# pwm-enable.net
KiCad netlist of a schematic drawn in Altium Designer
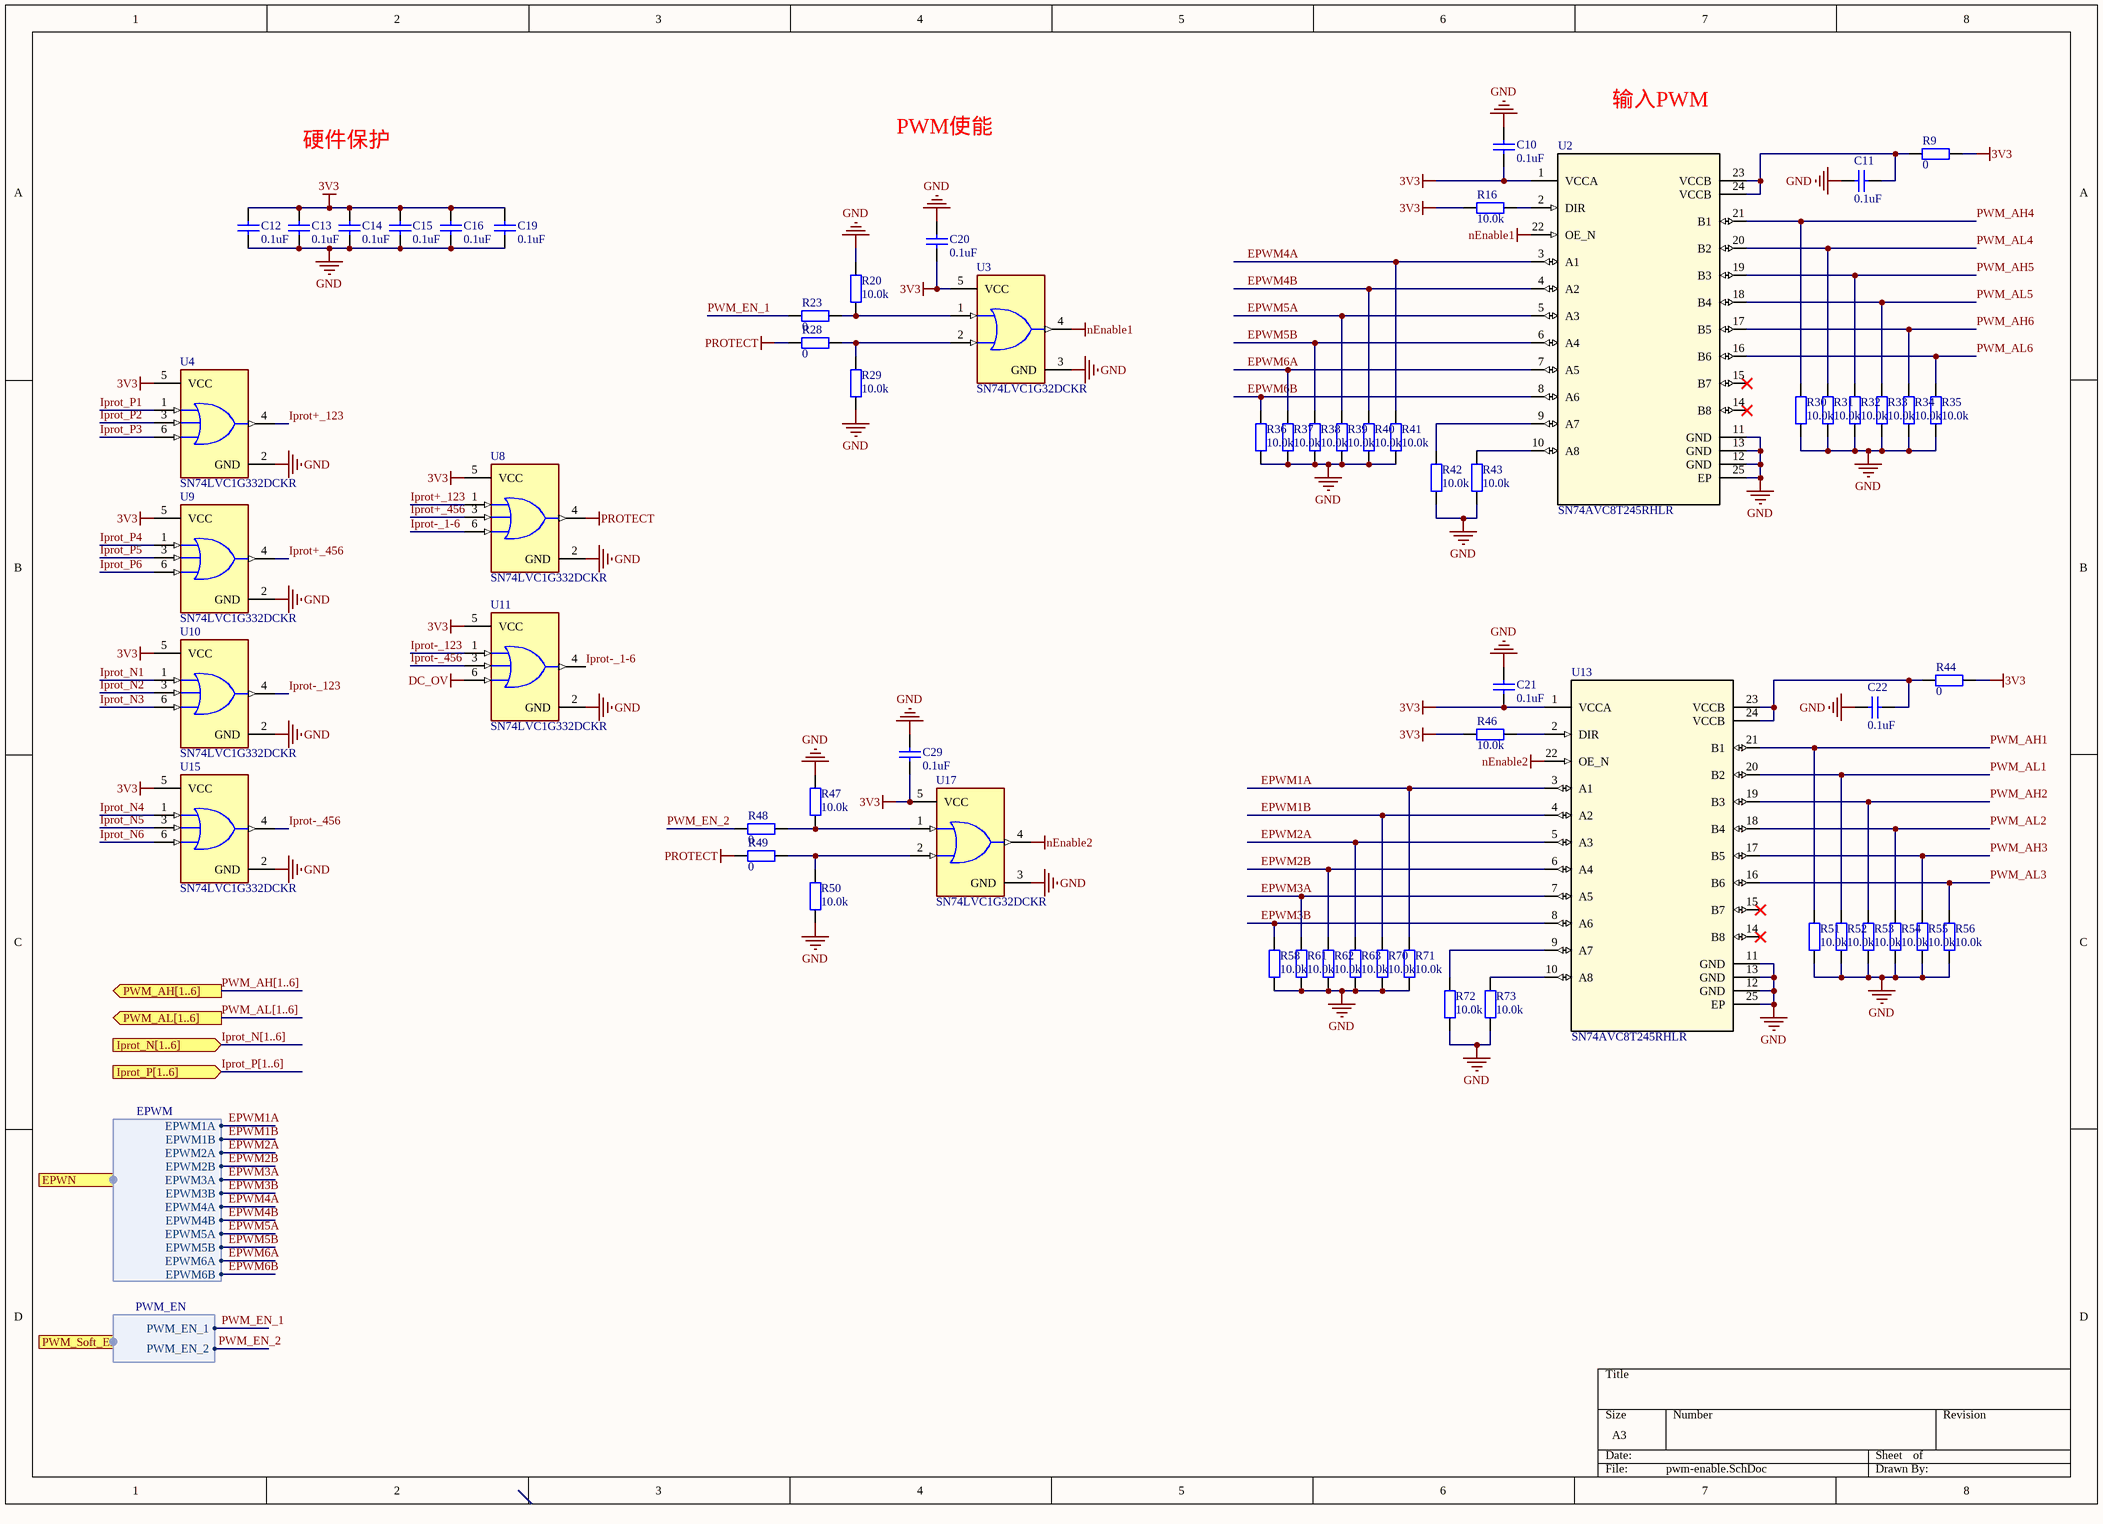
[diagram p0: pwm-enable.SchDoc]

(export (version "E")
  (design (tool "Eeschema 10.0.6"))
  (components
    (comp (ref "C10")
      (value "0.1uF")
      (footprint "CAPC1608X06N")
      (description "Capacitor")
      (fields (field (name "PUBLISHER") "Altium Limited"))
      (libsource (lib "Simscale") (part "Cap"))
    )
    (comp (ref "C11")
      (value "0.1uF")
      (footprint "CAPC1608X06N")
      (description "Capacitor")
      (fields (field (name "PUBLISHER") "Altium Limited"))
      (libsource (lib "Simscale") (part "Cap"))
    )
    (comp (ref "C12")
      (value "0.1uF")
      (footprint "CAPC1608X06N")
      (description "Capacitor")
      (fields (field (name "PUBLISHER") "Altium Limited"))
      (libsource (lib "Simscale") (part "Cap"))
    )
    (comp (ref "C13")
      (value "0.1uF")
      (footprint "CAPC1608X06N")
      (description "Capacitor")
      (fields (field (name "PUBLISHER") "Altium Limited"))
      (libsource (lib "Simscale") (part "Cap"))
    )
    (comp (ref "C14")
      (value "0.1uF")
      (footprint "CAPC1608X06N")
      (description "Capacitor")
      (fields (field (name "PUBLISHER") "Altium Limited"))
      (libsource (lib "Simscale") (part "Cap"))
    )
    (comp (ref "C15")
      (value "0.1uF")
      (footprint "CAPC1608X06N")
      (description "Capacitor")
      (fields (field (name "PUBLISHER") "Altium Limited"))
      (libsource (lib "Simscale") (part "Cap"))
    )
    (comp (ref "C16")
      (value "0.1uF")
      (footprint "CAPC1608X06N")
      (description "Capacitor")
      (fields (field (name "PUBLISHER") "Altium Limited"))
      (libsource (lib "Simscale") (part "Cap"))
    )
    (comp (ref "C19")
      (value "0.1uF")
      (footprint "CAPC1608X06N")
      (description "Capacitor")
      (fields (field (name "PUBLISHER") "Altium Limited"))
      (libsource (lib "Simscale") (part "Cap"))
    )
    (comp (ref "C20")
      (value "0.1uF")
      (footprint "CAPC1608X06N")
      (description "Capacitor")
      (fields (field (name "PUBLISHER") "Altium Limited"))
      (libsource (lib "Simscale") (part "Cap"))
    )
    (comp (ref "C21")
      (value "0.1uF")
      (footprint "CAPC1608X06N")
      (description "Capacitor")
      (fields (field (name "PUBLISHER") "Altium Limited"))
      (libsource (lib "Simscale") (part "Cap"))
    )
    (comp (ref "C22")
      (value "0.1uF")
      (footprint "CAPC1608X06N")
      (description "Capacitor")
      (fields (field (name "PUBLISHER") "Altium Limited"))
      (libsource (lib "Simscale") (part "Cap"))
    )
    (comp (ref "C29")
      (value "0.1uF")
      (footprint "CAPC1608X06N")
      (description "Capacitor")
      (fields (field (name "PUBLISHER") "Altium Limited"))
      (libsource (lib "Simscale") (part "Cap"))
    )
    (comp (ref "R9")
      (value "0")
      (footprint "RESC1608X05N")
      (description "Resistor 0402")
      (fields (field (name "PUBLISHER") "Altium Limited"))
      (libsource (lib "Soardra") (part "Res"))
    )
    (comp (ref "R16")
      (value "10.0k")
      (footprint "RESC1608X05N")
      (description "贴片电阻")
      (libsource (lib "") (part "0603 100KΩ (1003) 1%_4_1"))
    )
    (comp (ref "R20")
      (value "10.0k")
      (footprint "RESC1608X05N")
      (description "贴片电阻")
      (libsource (lib "") (part "0603 100KΩ (1003) 1%_4_2"))
    )
    (comp (ref "R23")
      (value "0")
      (footprint "RESC1608X05N")
      (description "贴片电阻")
      (libsource (lib "") (part "0603 100KΩ (1003) 1%_4_1"))
    )
    (comp (ref "R28")
      (value "0")
      (footprint "RESC1608X05N")
      (description "贴片电阻")
      (libsource (lib "") (part "0603 100KΩ (1003) 1%_4_1"))
    )
    (comp (ref "R29")
      (value "10.0k")
      (footprint "RESC1608X05N")
      (description "贴片电阻")
      (libsource (lib "Simscale") (part "0603 100KΩ (1003) 1%_4"))
    )
    (comp (ref "R30")
      (value "10.0k")
      (footprint "RESC1608X05N")
      (description "贴片电阻")
      (libsource (lib "") (part "0603 100KΩ (1003) 1%_4_2"))
    )
    (comp (ref "R31")
      (value "10.0k")
      (footprint "RESC1608X05N")
      (description "贴片电阻")
      (libsource (lib "") (part "0603 100KΩ (1003) 1%_4_2"))
    )
    (comp (ref "R32")
      (value "10.0k")
      (footprint "RESC1608X05N")
      (description "贴片电阻")
      (libsource (lib "") (part "0603 100KΩ (1003) 1%_4_2"))
    )
    (comp (ref "R33")
      (value "10.0k")
      (footprint "RESC1608X05N")
      (description "贴片电阻")
      (libsource (lib "") (part "0603 100KΩ (1003) 1%_4_2"))
    )
    (comp (ref "R34")
      (value "10.0k")
      (footprint "RESC1608X05N")
      (description "贴片电阻")
      (libsource (lib "") (part "0603 100KΩ (1003) 1%_4_2"))
    )
    (comp (ref "R35")
      (value "10.0k")
      (footprint "RESC1608X05N")
      (description "贴片电阻")
      (libsource (lib "") (part "0603 100KΩ (1003) 1%_4_2"))
    )
    (comp (ref "R36")
      (value "10.0k")
      (footprint "RESC1608X05N")
      (description "贴片电阻")
      (libsource (lib "Simscale") (part "0603 100KΩ (1003) 1%_4"))
    )
    (comp (ref "R37")
      (value "10.0k")
      (footprint "RESC1608X05N")
      (description "贴片电阻")
      (libsource (lib "Simscale") (part "0603 100KΩ (1003) 1%_4"))
    )
    (comp (ref "R38")
      (value "10.0k")
      (footprint "RESC1608X05N")
      (description "贴片电阻")
      (libsource (lib "Simscale") (part "0603 100KΩ (1003) 1%_4"))
    )
    (comp (ref "R39")
      (value "10.0k")
      (footprint "RESC1608X05N")
      (description "贴片电阻")
      (libsource (lib "") (part "0603 100KΩ (1003) 1%_4_2"))
    )
    (comp (ref "R40")
      (value "10.0k")
      (footprint "RESC1608X05N")
      (description "贴片电阻")
      (libsource (lib "Simscale") (part "0603 100KΩ (1003) 1%_4"))
    )
    (comp (ref "R41")
      (value "10.0k")
      (footprint "RESC1608X05N")
      (description "贴片电阻")
      (libsource (lib "Simscale") (part "0603 100KΩ (1003) 1%_4"))
    )
    (comp (ref "R42")
      (value "10.0k")
      (footprint "RESC1608X05N")
      (description "贴片电阻")
      (libsource (lib "") (part "0603 100KΩ (1003) 1%_4_2"))
    )
    (comp (ref "R43")
      (value "10.0k")
      (footprint "RESC1608X05N")
      (description "贴片电阻")
      (libsource (lib "") (part "0603 100KΩ (1003) 1%_4_2"))
    )
    (comp (ref "R44")
      (value "0")
      (footprint "RESC1608X05N")
      (description "Resistor 0402")
      (fields (field (name "PUBLISHER") "Altium Limited"))
      (libsource (lib "Soardra") (part "Res"))
    )
    (comp (ref "R46")
      (value "10.0k")
      (footprint "RESC1608X05N")
      (description "贴片电阻")
      (libsource (lib "") (part "0603 100KΩ (1003) 1%_4_1"))
    )
    (comp (ref "R47")
      (value "10.0k")
      (footprint "RESC1608X05N")
      (description "贴片电阻")
      (libsource (lib "") (part "0603 100KΩ (1003) 1%_4_2"))
    )
    (comp (ref "R48")
      (value "0")
      (footprint "RESC1608X05N")
      (description "贴片电阻")
      (libsource (lib "") (part "0603 100KΩ (1003) 1%_4_1"))
    )
    (comp (ref "R49")
      (value "0")
      (footprint "RESC1608X05N")
      (description "贴片电阻")
      (libsource (lib "") (part "0603 100KΩ (1003) 1%_4_1"))
    )
    (comp (ref "R50")
      (value "10.0k")
      (footprint "RESC1608X05N")
      (description "贴片电阻")
      (libsource (lib "Simscale") (part "0603 100KΩ (1003) 1%_4"))
    )
    (comp (ref "R51")
      (value "10.0k")
      (footprint "RESC1608X05N")
      (description "贴片电阻")
      (libsource (lib "") (part "0603 100KΩ (1003) 1%_4_2"))
    )
    (comp (ref "R52")
      (value "10.0k")
      (footprint "RESC1608X05N")
      (description "贴片电阻")
      (libsource (lib "") (part "0603 100KΩ (1003) 1%_4_2"))
    )
    (comp (ref "R53")
      (value "10.0k")
      (footprint "RESC1608X05N")
      (description "贴片电阻")
      (libsource (lib "") (part "0603 100KΩ (1003) 1%_4_2"))
    )
    (comp (ref "R54")
      (value "10.0k")
      (footprint "RESC1608X05N")
      (description "贴片电阻")
      (libsource (lib "") (part "0603 100KΩ (1003) 1%_4_2"))
    )
    (comp (ref "R55")
      (value "10.0k")
      (footprint "RESC1608X05N")
      (description "贴片电阻")
      (libsource (lib "") (part "0603 100KΩ (1003) 1%_4_2"))
    )
    (comp (ref "R56")
      (value "10.0k")
      (footprint "RESC1608X05N")
      (description "贴片电阻")
      (libsource (lib "") (part "0603 100KΩ (1003) 1%_4_2"))
    )
    (comp (ref "R58")
      (value "10.0k")
      (footprint "RESC1608X05N")
      (description "贴片电阻")
      (libsource (lib "Simscale") (part "0603 100KΩ (1003) 1%_4"))
    )
    (comp (ref "R61")
      (value "10.0k")
      (footprint "RESC1608X05N")
      (description "贴片电阻")
      (libsource (lib "Simscale") (part "0603 100KΩ (1003) 1%_4"))
    )
    (comp (ref "R62")
      (value "10.0k")
      (footprint "RESC1608X05N")
      (description "贴片电阻")
      (libsource (lib "Simscale") (part "0603 100KΩ (1003) 1%_4"))
    )
    (comp (ref "R63")
      (value "10.0k")
      (footprint "RESC1608X05N")
      (description "贴片电阻")
      (libsource (lib "") (part "0603 100KΩ (1003) 1%_4_2"))
    )
    (comp (ref "R70")
      (value "10.0k")
      (footprint "RESC1608X05N")
      (description "贴片电阻")
      (libsource (lib "Simscale") (part "0603 100KΩ (1003) 1%_4"))
    )
    (comp (ref "R71")
      (value "10.0k")
      (footprint "RESC1608X05N")
      (description "贴片电阻")
      (libsource (lib "Simscale") (part "0603 100KΩ (1003) 1%_4"))
    )
    (comp (ref "R72")
      (value "10.0k")
      (footprint "RESC1608X05N")
      (description "贴片电阻")
      (libsource (lib "") (part "0603 100KΩ (1003) 1%_4_2"))
    )
    (comp (ref "R73")
      (value "10.0k")
      (footprint "RESC1608X05N")
      (description "贴片电阻")
      (libsource (lib "") (part "0603 100KΩ (1003) 1%_4_2"))
    )
    (comp (ref "U2")
      (value "SN74AVC8T245RHLR")
      (footprint "RHL0024A")
      (description "No Description Available(1.2-3.6V)")
      (fields
        (field (name "PARTNUMBER") "SN74AVC8T245RHL")
        (field (name "MANUFACTURER") "Texas Instruments")
        (field (name "COPYRIGHT") "Copyright (C) 2024 Ultra Librarian. All rights reserved.")
      )
      (libsource (lib "aaa1") (part "SN74AVC8T245RHLR"))
    )
    (comp (ref "U3")
      (value "SN74LVC1G32DCKR")
      (footprint "FP-DCK0005A-IPC_A")
      (description "IC GATE OR 1CH 2-INP SC70-5(1.65-5.5V)")
      (libsource (lib "Altium Content Vault") (part "9a4003fa4a62225b3c2fa1ca1eebe37"))
    )
    (comp (ref "U4")
      (value "SN74LVC1G332DCKR")
      (footprint "FP-DCK0006A-MFG")
      (description "IC GATE OR 1CH 3-INP SC70-6")
      (fields
        (field (name "MANUFACTURER") "Texas Instruments")
        (field (name "OCTOPART") "https://octopart.com/sn74lvc1g332dckr-texas+instruments-464861")
      )
      (libsource (lib "Altium Content Vault") (part "a1fbee6839145229a27344b52c53a8d"))
    )
    (comp (ref "U8")
      (value "SN74LVC1G332DCKR")
      (footprint "FP-DCK0006A-MFG")
      (description "IC GATE OR 1CH 3-INP SC70-6")
      (fields
        (field (name "MANUFACTURER") "Texas Instruments")
        (field (name "OCTOPART") "https://octopart.com/sn74lvc1g332dckr-texas+instruments-464861")
      )
      (libsource (lib "Altium Content Vault") (part "a1fbee6839145229a27344b52c53a8d"))
    )
    (comp (ref "U9")
      (value "SN74LVC1G332DCKR")
      (footprint "FP-DCK0006A-MFG")
      (description "IC GATE OR 1CH 3-INP SC70-6")
      (fields
        (field (name "MANUFACTURER") "Texas Instruments")
        (field (name "OCTOPART") "https://octopart.com/sn74lvc1g332dckr-texas+instruments-464861")
      )
      (libsource (lib "Altium Content Vault") (part "a1fbee6839145229a27344b52c53a8d"))
    )
    (comp (ref "U10")
      (value "SN74LVC1G332DCKR")
      (footprint "FP-DCK0006A-MFG")
      (description "IC GATE OR 1CH 3-INP SC70-6")
      (fields
        (field (name "MANUFACTURER") "Texas Instruments")
        (field (name "OCTOPART") "https://octopart.com/sn74lvc1g332dckr-texas+instruments-464861")
      )
      (libsource (lib "Altium Content Vault") (part "a1fbee6839145229a27344b52c53a8d"))
    )
    (comp (ref "U11")
      (value "SN74LVC1G332DCKR")
      (footprint "FP-DCK0006A-MFG")
      (description "IC GATE OR 1CH 3-INP SC70-6")
      (fields
        (field (name "MANUFACTURER") "Texas Instruments")
        (field (name "OCTOPART") "https://octopart.com/sn74lvc1g332dckr-texas+instruments-464861")
      )
      (libsource (lib "Altium Content Vault") (part "a1fbee6839145229a27344b52c53a8d"))
    )
    (comp (ref "U13")
      (value "SN74AVC8T245RHLR")
      (footprint "RHL0024A")
      (description "No Description Available")
      (fields
        (field (name "PARTNUMBER") "SN74AVC8T245RHL")
        (field (name "MANUFACTURER") "Texas Instruments")
        (field (name "COPYRIGHT") "Copyright (C) 2024 Ultra Librarian. All rights reserved.")
      )
      (libsource (lib "aaa1") (part "SN74AVC8T245RHLR"))
    )
    (comp (ref "U15")
      (value "SN74LVC1G332DCKR")
      (footprint "FP-DCK0006A-MFG")
      (description "IC GATE OR 1CH 3-INP SC70-6")
      (fields
        (field (name "MANUFACTURER") "Texas Instruments")
        (field (name "OCTOPART") "https://octopart.com/sn74lvc1g332dckr-texas+instruments-464861")
      )
      (libsource (lib "Altium Content Vault") (part "a1fbee6839145229a27344b52c53a8d"))
    )
    (comp (ref "U17")
      (value "SN74LVC1G32DCKR")
      (footprint "FP-DCK0005A-IPC_A")
      (description "IC GATE OR 1CH 2-INP SC70-5(1.65-5.5V)")
      (libsource (lib "Altium Content Vault") (part "9a4003fa4a62225b3c2fa1ca1eebe37"))
    )
  )
  (nets
    (net (code "3") (name "/EPWM1A") (class "Default")
      (node (ref "R71") (pin "2") (pinfunction "2_2") (pintype "passive"))
      (node (ref "U13") (pin "3") (pinfunction "A1_3") (pintype "bidirectional"))
    )
    (net (code "4") (name "/EPWM1B") (class "Default")
      (node (ref "R70") (pin "2") (pinfunction "2_2") (pintype "passive"))
      (node (ref "U13") (pin "4") (pinfunction "A2_4") (pintype "bidirectional"))
    )
    (net (code "5") (name "/EPWM2A") (class "Default")
      (node (ref "R63") (pin "1") (pinfunction "1_1") (pintype "passive"))
      (node (ref "U13") (pin "5") (pinfunction "A3_5") (pintype "bidirectional"))
    )
    (net (code "6") (name "/EPWM2B") (class "Default")
      (node (ref "R62") (pin "2") (pinfunction "2_2") (pintype "passive"))
      (node (ref "U13") (pin "6") (pinfunction "A4_6") (pintype "bidirectional"))
    )
    (net (code "7") (name "/EPWM3A") (class "Default")
      (node (ref "R61") (pin "2") (pinfunction "2_2") (pintype "passive"))
      (node (ref "U13") (pin "7") (pinfunction "A5_7") (pintype "bidirectional"))
    )
    (net (code "8") (name "/EPWM3B") (class "Default")
      (node (ref "R58") (pin "2") (pinfunction "2_2") (pintype "passive"))
      (node (ref "U13") (pin "8") (pinfunction "A6_8") (pintype "bidirectional"))
    )
    (net (code "9") (name "/EPWM4A") (class "Default")
      (node (ref "R41") (pin "2") (pinfunction "2_2") (pintype "passive"))
      (node (ref "U2") (pin "3") (pinfunction "A1_3") (pintype "bidirectional"))
    )
    (net (code "10") (name "/EPWM4B") (class "Default")
      (node (ref "R40") (pin "2") (pinfunction "2_2") (pintype "passive"))
      (node (ref "U2") (pin "4") (pinfunction "A2_4") (pintype "bidirectional"))
    )
    (net (code "11") (name "/EPWM5A") (class "Default")
      (node (ref "R39") (pin "1") (pinfunction "1_1") (pintype "passive"))
      (node (ref "U2") (pin "5") (pinfunction "A3_5") (pintype "bidirectional"))
    )
    (net (code "12") (name "/EPWM5B") (class "Default")
      (node (ref "R38") (pin "2") (pinfunction "2_2") (pintype "passive"))
      (node (ref "U2") (pin "6") (pinfunction "A4_6") (pintype "bidirectional"))
    )
    (net (code "13") (name "/EPWM6A") (class "Default")
      (node (ref "R37") (pin "2") (pinfunction "2_2") (pintype "passive"))
      (node (ref "U2") (pin "7") (pinfunction "A5_7") (pintype "bidirectional"))
    )
    (net (code "14") (name "/EPWM6B") (class "Default")
      (node (ref "R36") (pin "2") (pinfunction "2_2") (pintype "passive"))
      (node (ref "U2") (pin "8") (pinfunction "A6_8") (pintype "bidirectional"))
    )
    (net (code "15") (name "/Iprot+_123") (class "Default")
      (node (ref "U4") (pin "4") (pinfunction "Y_4") (pintype "output"))
      (node (ref "U8") (pin "1") (pinfunction "A_1") (pintype "input"))
    )
    (net (code "16") (name "/Iprot+_456") (class "Default")
      (node (ref "U8") (pin "3") (pinfunction "B_3") (pintype "input"))
      (node (ref "U9") (pin "4") (pinfunction "Y_4") (pintype "output"))
    )
    (net (code "17") (name "/Iprot-_1-6") (class "Default")
      (node (ref "U11") (pin "4") (pinfunction "Y_4") (pintype "output"))
      (node (ref "U8") (pin "6") (pinfunction "C_6") (pintype "input"))
    )
    (net (code "18") (name "/Iprot-_123") (class "Default")
      (node (ref "U10") (pin "4") (pinfunction "Y_4") (pintype "output"))
      (node (ref "U11") (pin "1") (pinfunction "A_1") (pintype "input"))
    )
    (net (code "19") (name "/Iprot-_456") (class "Default")
      (node (ref "U11") (pin "3") (pinfunction "B_3") (pintype "input"))
      (node (ref "U15") (pin "4") (pinfunction "Y_4") (pintype "output"))
    )
    (net (code "20") (name "/Iprot_N1") (class "Default")
      (node (ref "U10") (pin "1") (pinfunction "A_1") (pintype "input"))
    )
    (net (code "21") (name "/Iprot_N2") (class "Default")
      (node (ref "U10") (pin "3") (pinfunction "B_3") (pintype "input"))
    )
    (net (code "22") (name "/Iprot_N3") (class "Default")
      (node (ref "U10") (pin "6") (pinfunction "C_6") (pintype "input"))
    )
    (net (code "23") (name "/Iprot_N4") (class "Default")
      (node (ref "U15") (pin "1") (pinfunction "A_1") (pintype "input"))
    )
    (net (code "24") (name "/Iprot_N5") (class "Default")
      (node (ref "U15") (pin "3") (pinfunction "B_3") (pintype "input"))
    )
    (net (code "25") (name "/Iprot_N6") (class "Default")
      (node (ref "U15") (pin "6") (pinfunction "C_6") (pintype "input"))
    )
    (net (code "27") (name "/Iprot_P1") (class "Default")
      (node (ref "U4") (pin "1") (pinfunction "A_1") (pintype "input"))
    )
    (net (code "28") (name "/Iprot_P2") (class "Default")
      (node (ref "U4") (pin "3") (pinfunction "B_3") (pintype "input"))
    )
    (net (code "29") (name "/Iprot_P3") (class "Default")
      (node (ref "U4") (pin "6") (pinfunction "C_6") (pintype "input"))
    )
    (net (code "30") (name "/Iprot_P4") (class "Default")
      (node (ref "U9") (pin "1") (pinfunction "A_1") (pintype "input"))
    )
    (net (code "31") (name "/Iprot_P5") (class "Default")
      (node (ref "U9") (pin "3") (pinfunction "B_3") (pintype "input"))
    )
    (net (code "32") (name "/Iprot_P6") (class "Default")
      (node (ref "U9") (pin "6") (pinfunction "C_6") (pintype "input"))
    )
    (net (code "34") (name "/PWM_AH1") (class "Default")
      (node (ref "R51") (pin "1") (pinfunction "1_1") (pintype "passive"))
      (node (ref "U13") (pin "21") (pinfunction "B1_21") (pintype "bidirectional"))
    )
    (net (code "35") (name "/PWM_AH2") (class "Default")
      (node (ref "R53") (pin "1") (pinfunction "1_1") (pintype "passive"))
      (node (ref "U13") (pin "19") (pinfunction "B3_19") (pintype "bidirectional"))
    )
    (net (code "36") (name "/PWM_AH3") (class "Default")
      (node (ref "R55") (pin "1") (pinfunction "1_1") (pintype "passive"))
      (node (ref "U13") (pin "17") (pinfunction "B5_17") (pintype "bidirectional"))
    )
    (net (code "37") (name "/PWM_AH4") (class "Default")
      (node (ref "R30") (pin "1") (pinfunction "1_1") (pintype "passive"))
      (node (ref "U2") (pin "21") (pinfunction "B1_21") (pintype "bidirectional"))
    )
    (net (code "38") (name "/PWM_AH5") (class "Default")
      (node (ref "R32") (pin "1") (pinfunction "1_1") (pintype "passive"))
      (node (ref "U2") (pin "19") (pinfunction "B3_19") (pintype "bidirectional"))
    )
    (net (code "39") (name "/PWM_AH6") (class "Default")
      (node (ref "R34") (pin "1") (pinfunction "1_1") (pintype "passive"))
      (node (ref "U2") (pin "17") (pinfunction "B5_17") (pintype "bidirectional"))
    )
    (net (code "41") (name "/PWM_AL1") (class "Default")
      (node (ref "R52") (pin "1") (pinfunction "1_1") (pintype "passive"))
      (node (ref "U13") (pin "20") (pinfunction "B2_20") (pintype "bidirectional"))
    )
    (net (code "42") (name "/PWM_AL2") (class "Default")
      (node (ref "R54") (pin "1") (pinfunction "1_1") (pintype "passive"))
      (node (ref "U13") (pin "18") (pinfunction "B4_18") (pintype "bidirectional"))
    )
    (net (code "43") (name "/PWM_AL3") (class "Default")
      (node (ref "R56") (pin "1") (pinfunction "1_1") (pintype "passive"))
      (node (ref "U13") (pin "16") (pinfunction "B6_16") (pintype "bidirectional"))
    )
    (net (code "44") (name "/PWM_AL4") (class "Default")
      (node (ref "R31") (pin "1") (pinfunction "1_1") (pintype "passive"))
      (node (ref "U2") (pin "20") (pinfunction "B2_20") (pintype "bidirectional"))
    )
    (net (code "45") (name "/PWM_AL5") (class "Default")
      (node (ref "R33") (pin "1") (pinfunction "1_1") (pintype "passive"))
      (node (ref "U2") (pin "18") (pinfunction "B4_18") (pintype "bidirectional"))
    )
    (net (code "46") (name "/PWM_AL6") (class "Default")
      (node (ref "R35") (pin "1") (pinfunction "1_1") (pintype "passive"))
      (node (ref "U2") (pin "16") (pinfunction "B6_16") (pintype "bidirectional"))
    )
    (net (code "48") (name "/PWM_EN_1") (class "Default")
      (node (ref "R23") (pin "1") (pinfunction "1_1") (pintype "passive"))
    )
    (net (code "49") (name "/PWM_EN_2") (class "Default")
      (node (ref "R48") (pin "1") (pinfunction "1_1") (pintype "passive"))
    )
    (net (code "52") (name "3V3") (class "Default")
      (node (ref "C10") (pin "1") (pinfunction "1_1") (pintype "passive"))
      (node (ref "C12") (pin "1") (pinfunction "1_1") (pintype "passive"))
      (node (ref "C13") (pin "1") (pinfunction "1_1") (pintype "passive"))
      (node (ref "C14") (pin "1") (pinfunction "1_1") (pintype "passive"))
      (node (ref "C15") (pin "1") (pinfunction "1_1") (pintype "passive"))
      (node (ref "C16") (pin "1") (pinfunction "1_1") (pintype "passive"))
      (node (ref "C19") (pin "1") (pinfunction "1_1") (pintype "passive"))
      (node (ref "C20") (pin "1") (pinfunction "1_1") (pintype "passive"))
      (node (ref "C21") (pin "1") (pinfunction "1_1") (pintype "passive"))
      (node (ref "C29") (pin "1") (pinfunction "1_1") (pintype "passive"))
      (node (ref "R16") (pin "1") (pinfunction "1_1") (pintype "passive"))
      (node (ref "R44") (pin "2") (pinfunction "2_2") (pintype "passive"))
      (node (ref "R46") (pin "1") (pinfunction "1_1") (pintype "passive"))
      (node (ref "R9") (pin "2") (pinfunction "2_2") (pintype "passive"))
      (node (ref "U10") (pin "5") (pinfunction "VCC_5") (pintype "power_in"))
      (node (ref "U11") (pin "5") (pinfunction "VCC_5") (pintype "power_in"))
      (node (ref "U13") (pin "1") (pinfunction "VCCA_1") (pintype "power_in"))
      (node (ref "U15") (pin "5") (pinfunction "VCC_5") (pintype "power_in"))
      (node (ref "U17") (pin "5") (pinfunction "VCC_5") (pintype "power_in"))
      (node (ref "U2") (pin "1") (pinfunction "VCCA_1") (pintype "power_in"))
      (node (ref "U3") (pin "5") (pinfunction "VCC_5") (pintype "power_in"))
      (node (ref "U4") (pin "5") (pinfunction "VCC_5") (pintype "power_in"))
      (node (ref "U8") (pin "5") (pinfunction "VCC_5") (pintype "power_in"))
      (node (ref "U9") (pin "5") (pinfunction "VCC_5") (pintype "power_in"))
    )
    (net (code "53") (name "DC_OV") (class "Default")
      (node (ref "U11") (pin "6") (pinfunction "C_6") (pintype "input"))
    )
    (net (code "54") (name "GND") (class "Default")
      (node (ref "C10") (pin "2") (pinfunction "2_2") (pintype "passive"))
      (node (ref "C11") (pin "2") (pinfunction "2_2") (pintype "passive"))
      (node (ref "C12") (pin "2") (pinfunction "2_2") (pintype "passive"))
      (node (ref "C13") (pin "2") (pinfunction "2_2") (pintype "passive"))
      (node (ref "C14") (pin "2") (pinfunction "2_2") (pintype "passive"))
      (node (ref "C15") (pin "2") (pinfunction "2_2") (pintype "passive"))
      (node (ref "C16") (pin "2") (pinfunction "2_2") (pintype "passive"))
      (node (ref "C19") (pin "2") (pinfunction "2_2") (pintype "passive"))
      (node (ref "C20") (pin "2") (pinfunction "2_2") (pintype "passive"))
      (node (ref "C21") (pin "2") (pinfunction "2_2") (pintype "passive"))
      (node (ref "C22") (pin "2") (pinfunction "2_2") (pintype "passive"))
      (node (ref "C29") (pin "2") (pinfunction "2_2") (pintype "passive"))
      (node (ref "R20") (pin "1") (pinfunction "1_1") (pintype "passive"))
      (node (ref "R29") (pin "1") (pinfunction "1_1") (pintype "passive"))
      (node (ref "R30") (pin "2") (pinfunction "2_2") (pintype "passive"))
      (node (ref "R31") (pin "2") (pinfunction "2_2") (pintype "passive"))
      (node (ref "R32") (pin "2") (pinfunction "2_2") (pintype "passive"))
      (node (ref "R33") (pin "2") (pinfunction "2_2") (pintype "passive"))
      (node (ref "R34") (pin "2") (pinfunction "2_2") (pintype "passive"))
      (node (ref "R35") (pin "2") (pinfunction "2_2") (pintype "passive"))
      (node (ref "R36") (pin "1") (pinfunction "1_1") (pintype "passive"))
      (node (ref "R37") (pin "1") (pinfunction "1_1") (pintype "passive"))
      (node (ref "R38") (pin "1") (pinfunction "1_1") (pintype "passive"))
      (node (ref "R39") (pin "2") (pinfunction "2_2") (pintype "passive"))
      (node (ref "R40") (pin "1") (pinfunction "1_1") (pintype "passive"))
      (node (ref "R41") (pin "1") (pinfunction "1_1") (pintype "passive"))
      (node (ref "R42") (pin "2") (pinfunction "2_2") (pintype "passive"))
      (node (ref "R43") (pin "2") (pinfunction "2_2") (pintype "passive"))
      (node (ref "R47") (pin "1") (pinfunction "1_1") (pintype "passive"))
      (node (ref "R50") (pin "1") (pinfunction "1_1") (pintype "passive"))
      (node (ref "R51") (pin "2") (pinfunction "2_2") (pintype "passive"))
      (node (ref "R52") (pin "2") (pinfunction "2_2") (pintype "passive"))
      (node (ref "R53") (pin "2") (pinfunction "2_2") (pintype "passive"))
      (node (ref "R54") (pin "2") (pinfunction "2_2") (pintype "passive"))
      (node (ref "R55") (pin "2") (pinfunction "2_2") (pintype "passive"))
      (node (ref "R56") (pin "2") (pinfunction "2_2") (pintype "passive"))
      (node (ref "R58") (pin "1") (pinfunction "1_1") (pintype "passive"))
      (node (ref "R61") (pin "1") (pinfunction "1_1") (pintype "passive"))
      (node (ref "R62") (pin "1") (pinfunction "1_1") (pintype "passive"))
      (node (ref "R63") (pin "2") (pinfunction "2_2") (pintype "passive"))
      (node (ref "R70") (pin "1") (pinfunction "1_1") (pintype "passive"))
      (node (ref "R71") (pin "1") (pinfunction "1_1") (pintype "passive"))
      (node (ref "R72") (pin "2") (pinfunction "2_2") (pintype "passive"))
      (node (ref "R73") (pin "2") (pinfunction "2_2") (pintype "passive"))
      (node (ref "U10") (pin "2") (pinfunction "GND_2") (pintype "power_in"))
      (node (ref "U11") (pin "2") (pinfunction "GND_2") (pintype "power_in"))
      (node (ref "U13") (pin "11") (pinfunction "GND_11") (pintype "power_in"))
      (node (ref "U13") (pin "12") (pinfunction "GND_12") (pintype "power_in"))
      (node (ref "U13") (pin "13") (pinfunction "GND_13") (pintype "power_in"))
      (node (ref "U13") (pin "25") (pinfunction "EP_25") (pintype "passive"))
      (node (ref "U15") (pin "2") (pinfunction "GND_2") (pintype "power_in"))
      (node (ref "U17") (pin "3") (pinfunction "GND_3") (pintype "power_in"))
      (node (ref "U2") (pin "11") (pinfunction "GND_11") (pintype "power_in"))
      (node (ref "U2") (pin "12") (pinfunction "GND_12") (pintype "power_in"))
      (node (ref "U2") (pin "13") (pinfunction "GND_13") (pintype "power_in"))
      (node (ref "U2") (pin "25") (pinfunction "EP_25") (pintype "passive"))
      (node (ref "U3") (pin "3") (pinfunction "GND_3") (pintype "power_in"))
      (node (ref "U4") (pin "2") (pinfunction "GND_2") (pintype "power_in"))
      (node (ref "U8") (pin "2") (pinfunction "GND_2") (pintype "power_in"))
      (node (ref "U9") (pin "2") (pinfunction "GND_2") (pintype "power_in"))
    )
    (net (code "55") (name "Net-(C11-Pad1)") (class "Default")
      (node (ref "C11") (pin "1") (pinfunction "1_1") (pintype "passive"))
      (node (ref "R9") (pin "1") (pinfunction "1_1") (pintype "passive"))
      (node (ref "U2") (pin "23") (pinfunction "VCCB_23") (pintype "power_in"))
      (node (ref "U2") (pin "24") (pinfunction "VCCB_24") (pintype "power_in"))
    )
    (net (code "56") (name "Net-(C22-Pad1)") (class "Default")
      (node (ref "C22") (pin "1") (pinfunction "1_1") (pintype "passive"))
      (node (ref "R44") (pin "1") (pinfunction "1_1") (pintype "passive"))
      (node (ref "U13") (pin "23") (pinfunction "VCCB_23") (pintype "power_in"))
      (node (ref "U13") (pin "24") (pinfunction "VCCB_24") (pintype "power_in"))
    )
    (net (code "57") (name "Net-(U2-A7)") (class "Default")
      (node (ref "R42") (pin "1") (pinfunction "1_1") (pintype "passive"))
      (node (ref "U2") (pin "9") (pinfunction "A7_9") (pintype "bidirectional"))
    )
    (net (code "58") (name "Net-(U2-A8)") (class "Default")
      (node (ref "R43") (pin "1") (pinfunction "1_1") (pintype "passive"))
      (node (ref "U2") (pin "10") (pinfunction "A8_10") (pintype "bidirectional"))
    )
    (net (code "59") (name "Net-(U2-DIR)") (class "Default")
      (node (ref "R16") (pin "2") (pinfunction "2_2") (pintype "passive"))
      (node (ref "U2") (pin "2") (pinfunction "DIR_2") (pintype "input"))
    )
    (net (code "60") (name "Net-(U3-A)") (class "Default")
      (node (ref "R20") (pin "2") (pinfunction "2_2") (pintype "passive"))
      (node (ref "R23") (pin "2") (pinfunction "2_2") (pintype "passive"))
      (node (ref "U3") (pin "1") (pinfunction "A_1") (pintype "input"))
    )
    (net (code "61") (name "Net-(U3-B)") (class "Default")
      (node (ref "R28") (pin "2") (pinfunction "2_2") (pintype "passive"))
      (node (ref "R29") (pin "2") (pinfunction "2_2") (pintype "passive"))
      (node (ref "U3") (pin "2") (pinfunction "B_2") (pintype "input"))
    )
    (net (code "62") (name "Net-(U13-A7)") (class "Default")
      (node (ref "R72") (pin "1") (pinfunction "1_1") (pintype "passive"))
      (node (ref "U13") (pin "9") (pinfunction "A7_9") (pintype "bidirectional"))
    )
    (net (code "63") (name "Net-(U13-A8)") (class "Default")
      (node (ref "R73") (pin "1") (pinfunction "1_1") (pintype "passive"))
      (node (ref "U13") (pin "10") (pinfunction "A8_10") (pintype "bidirectional"))
    )
    (net (code "64") (name "Net-(U13-DIR)") (class "Default")
      (node (ref "R46") (pin "2") (pinfunction "2_2") (pintype "passive"))
      (node (ref "U13") (pin "2") (pinfunction "DIR_2") (pintype "input"))
    )
    (net (code "65") (name "Net-(U17-A)") (class "Default")
      (node (ref "R47") (pin "2") (pinfunction "2_2") (pintype "passive"))
      (node (ref "R48") (pin "2") (pinfunction "2_2") (pintype "passive"))
      (node (ref "U17") (pin "1") (pinfunction "A_1") (pintype "input"))
    )
    (net (code "66") (name "Net-(U17-B)") (class "Default")
      (node (ref "R49") (pin "2") (pinfunction "2_2") (pintype "passive"))
      (node (ref "R50") (pin "2") (pinfunction "2_2") (pintype "passive"))
      (node (ref "U17") (pin "2") (pinfunction "B_2") (pintype "input"))
    )
    (net (code "67") (name "PROTECT") (class "Default")
      (node (ref "R28") (pin "1") (pinfunction "1_1") (pintype "passive"))
      (node (ref "R49") (pin "1") (pinfunction "1_1") (pintype "passive"))
      (node (ref "U8") (pin "4") (pinfunction "Y_4") (pintype "output"))
    )
    (net (code "68") (name "nEnable1") (class "Default")
      (node (ref "U2") (pin "22") (pinfunction "OE_N_22") (pintype "input"))
      (node (ref "U3") (pin "4") (pinfunction "Y_4") (pintype "output"))
    )
    (net (code "69") (name "nEnable2") (class "Default")
      (node (ref "U13") (pin "22") (pinfunction "OE_N_22") (pintype "input"))
      (node (ref "U17") (pin "4") (pinfunction "Y_4") (pintype "output"))
    )
    (net (code "70") (name "unconnected-(U2-B7-Pad15)") (class "Default")
      (node (ref "U2") (pin "15") (pinfunction "B7_15") (pintype "bidirectional+no_connect"))
    )
    (net (code "71") (name "unconnected-(U2-B8-Pad14)") (class "Default")
      (node (ref "U2") (pin "14") (pinfunction "B8_14") (pintype "bidirectional+no_connect"))
    )
    (net (code "72") (name "unconnected-(U13-B7-Pad15)") (class "Default")
      (node (ref "U13") (pin "15") (pinfunction "B7_15") (pintype "bidirectional+no_connect"))
    )
    (net (code "73") (name "unconnected-(U13-B8-Pad14)") (class "Default")
      (node (ref "U13") (pin "14") (pinfunction "B8_14") (pintype "bidirectional+no_connect"))
    )
  )
)
